# Trinkey-DualSwitch-Concept1.net
KiCad netlist of a schematic drawn in EAGLE
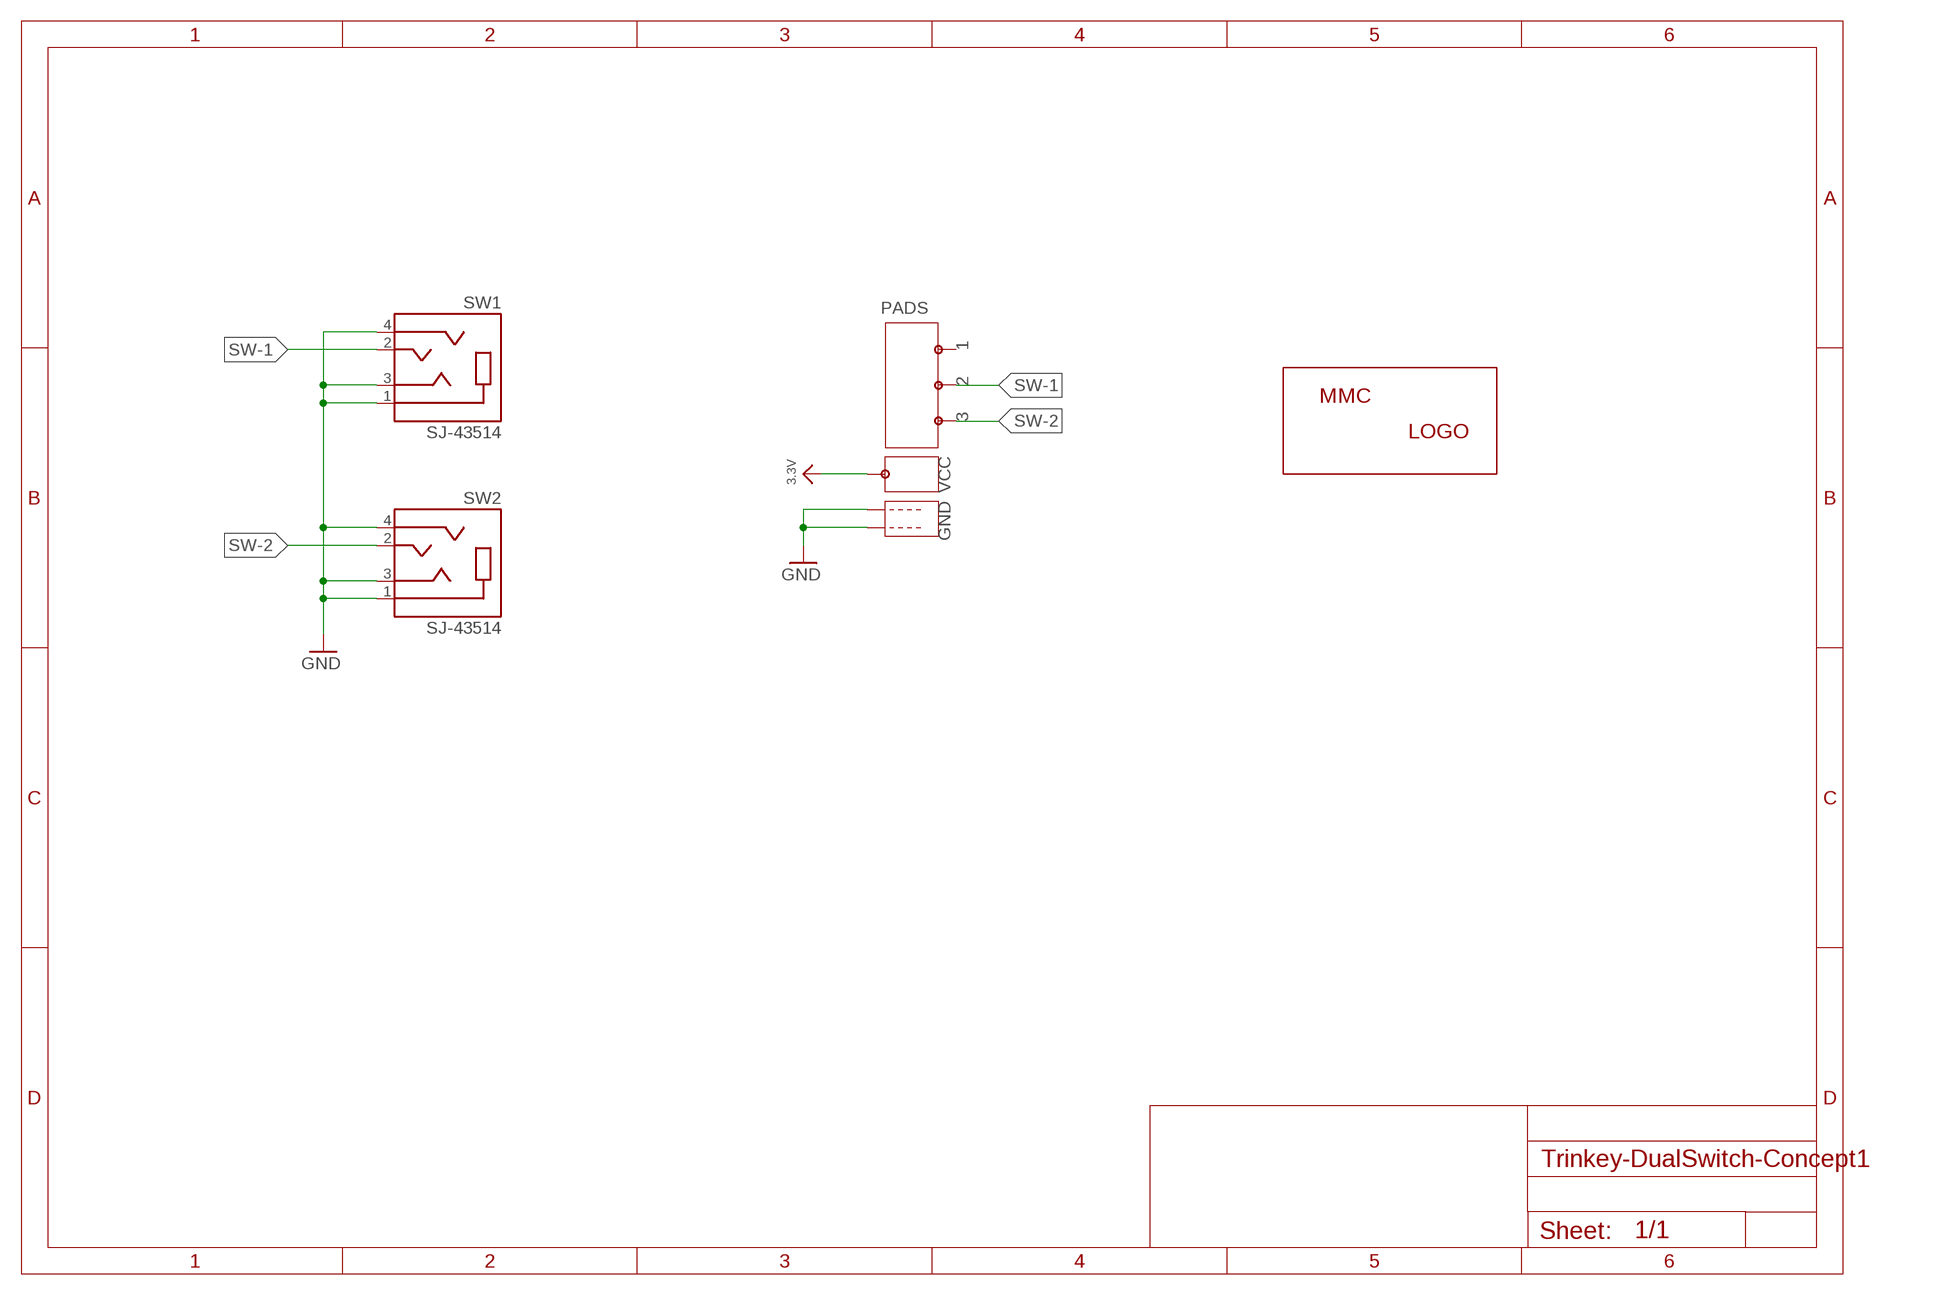
[diagram p0: schematic, sheet 1]

(export (version "E")
  (design (tool "Eeschema 10.0.6"))
  (components
    (comp (ref "LABEL_LOGO")
      (value "MMC_LOGO-XSM")
      (footprint "eagle-import:MMC_X-SMALL_LOGO")
      (libsource (lib "eagle-import") (part "MMC_LOGO-XSM"))
    )
    (comp (ref "PADS")
      (value "CASTELLATED-ROTARY-TRINKEY")
      (footprint "eagle-import:CASTELLATED-ROTARY-TRINKEY")
      (libsource (lib "eagle-import") (part "CASTELLATED-ROTARY-TRINKEY"))
    )
    (comp (ref "SW1")
      (value "SJ-43514")
      (footprint "eagle-import:CUI_SJ-43514")
      (libsource (lib "eagle-import") (part "SJ-43514"))
    )
    (comp (ref "SW2")
      (value "SJ-43514")
      (footprint "eagle-import:CUI_SJ-43514")
      (libsource (lib "eagle-import") (part "SJ-43514"))
    )
  )
  (nets
    (net (code "1") (name "3.3V") (class "Default")
      (node (ref "PADS") (pin "P$VCC") (pinfunction "P$VCC_P$VCC") (pintype "passive"))
    )
    (net (code "2") (name "GND") (class "Default")
      (node (ref "PADS") (pin "P$GND1") (pinfunction "P$GND1_P$GND1") (pintype "passive"))
      (node (ref "PADS") (pin "P$GND2") (pinfunction "P$GND2_P$GND2") (pintype "passive"))
      (node (ref "SW1") (pin "1") (pinfunction "SLEEVE_1") (pintype "passive"))
      (node (ref "SW1") (pin "3") (pinfunction "RING1_3") (pintype "passive"))
      (node (ref "SW1") (pin "4") (pinfunction "RING2_4") (pintype "passive"))
      (node (ref "SW2") (pin "1") (pinfunction "SLEEVE_1") (pintype "passive"))
      (node (ref "SW2") (pin "3") (pinfunction "RING1_3") (pintype "passive"))
      (node (ref "SW2") (pin "4") (pinfunction "RING2_4") (pintype "passive"))
    )
    (net (code "3") (name "SW-1") (class "Default")
      (node (ref "PADS") (pin "P$S2") (pinfunction "P$S2_P$S2") (pintype "passive"))
      (node (ref "SW1") (pin "2") (pinfunction "TIP_2") (pintype "passive"))
    )
    (net (code "4") (name "SW-2") (class "Default")
      (node (ref "PADS") (pin "P$S3") (pinfunction "P$S3_P$S3") (pintype "passive"))
      (node (ref "SW2") (pin "2") (pinfunction "TIP_2") (pintype "passive"))
    )
    (net (code "5") (name "unconnected-(PADS-PadP$S1)") (class "Default")
      (node (ref "PADS") (pin "P$S1") (pinfunction "P$S1_P$S1") (pintype "passive"))
    )
  )
)
